# MOTOR_DRIVER.net
KiCad netlist of a schematic drawn in EAGLE
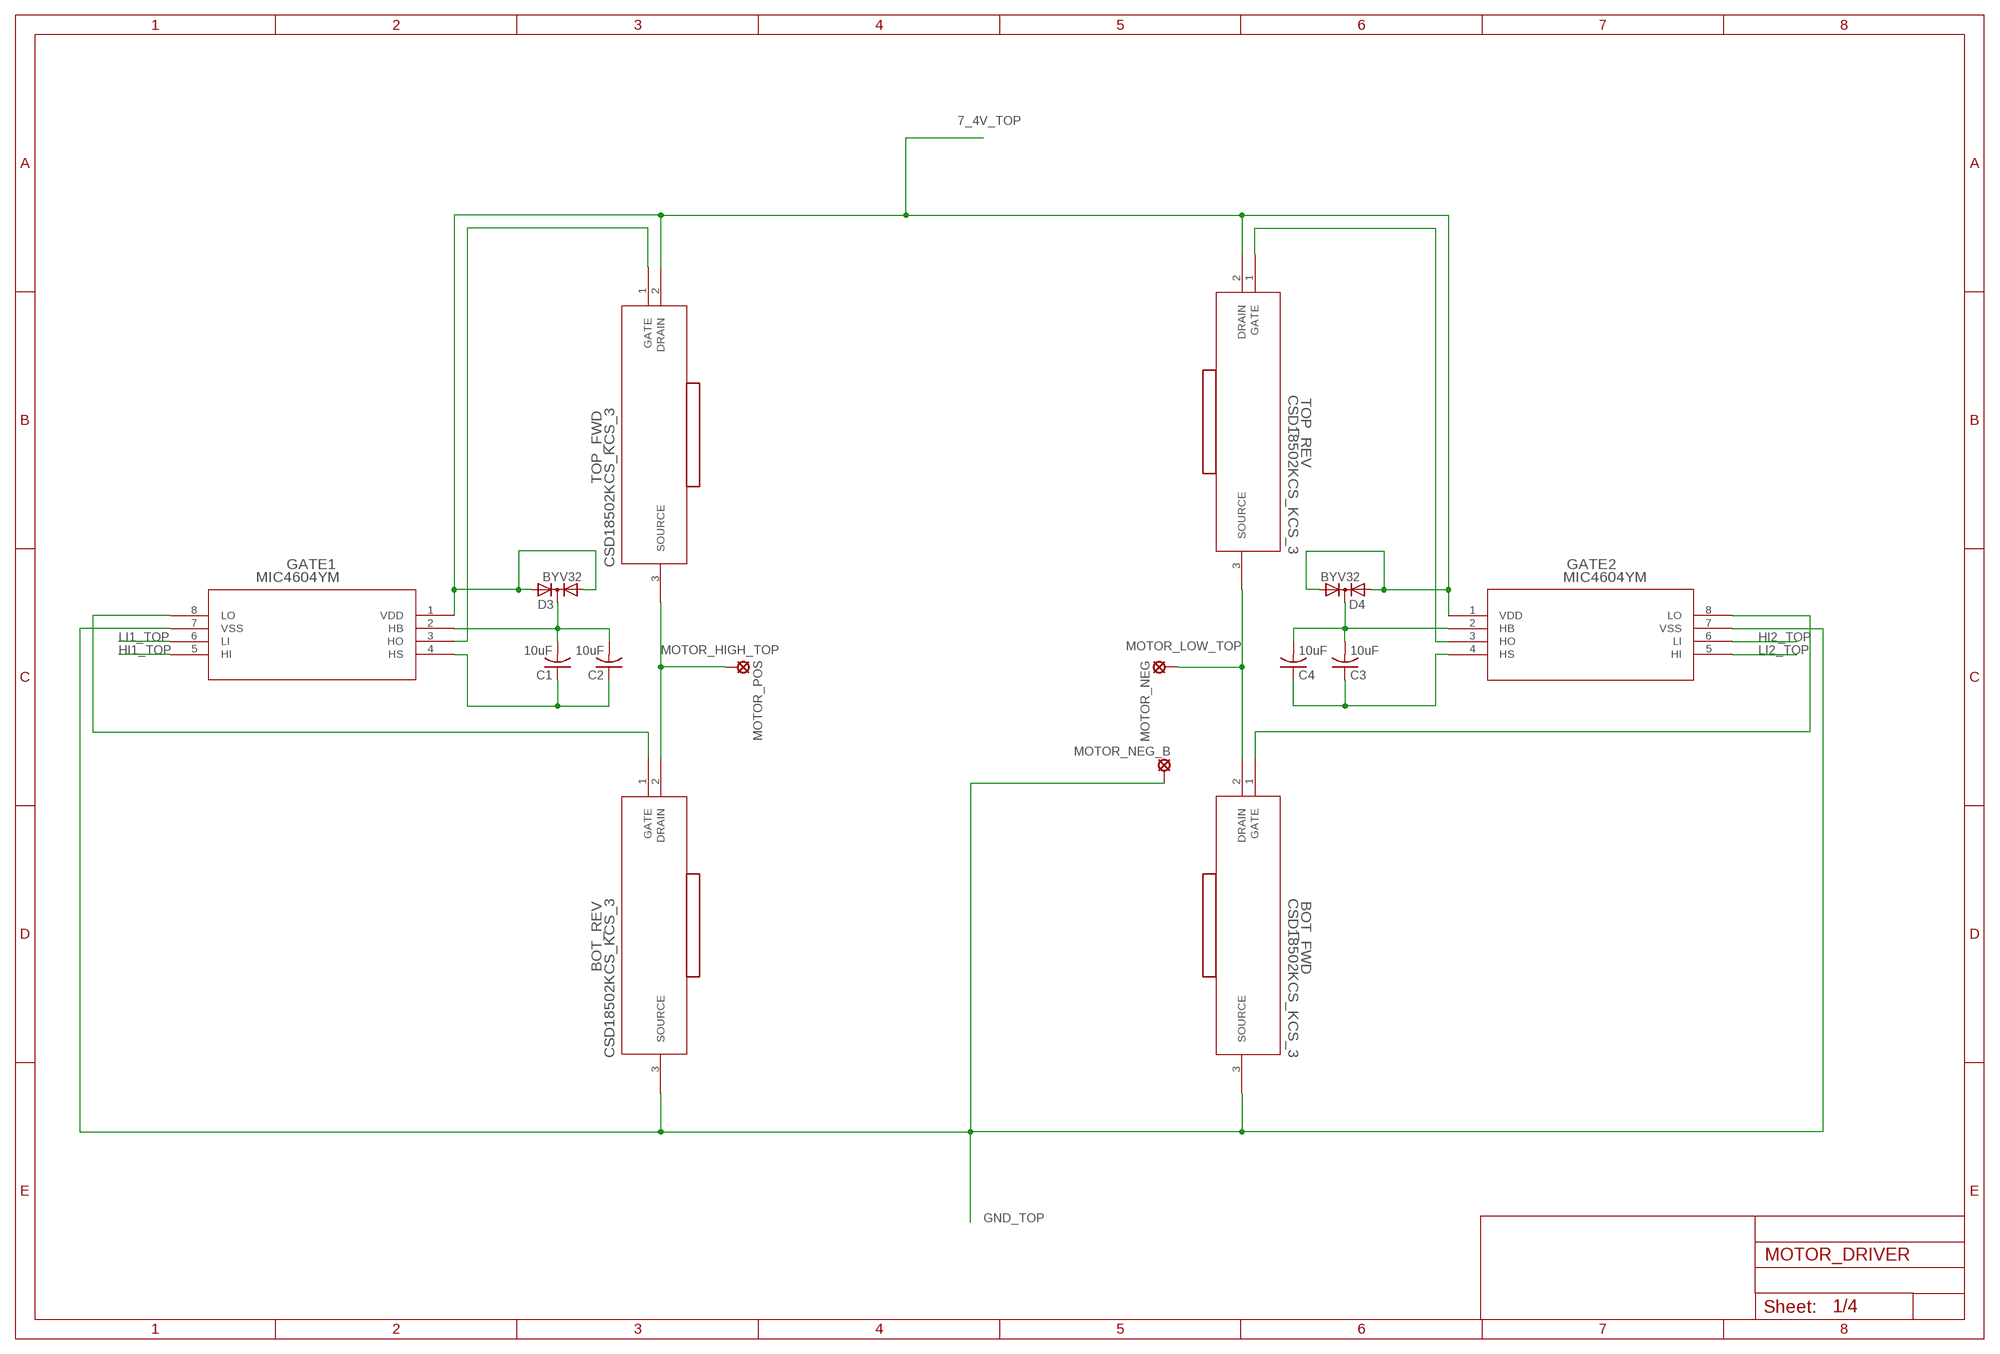
[diagram p0: schematic, sheet 1]
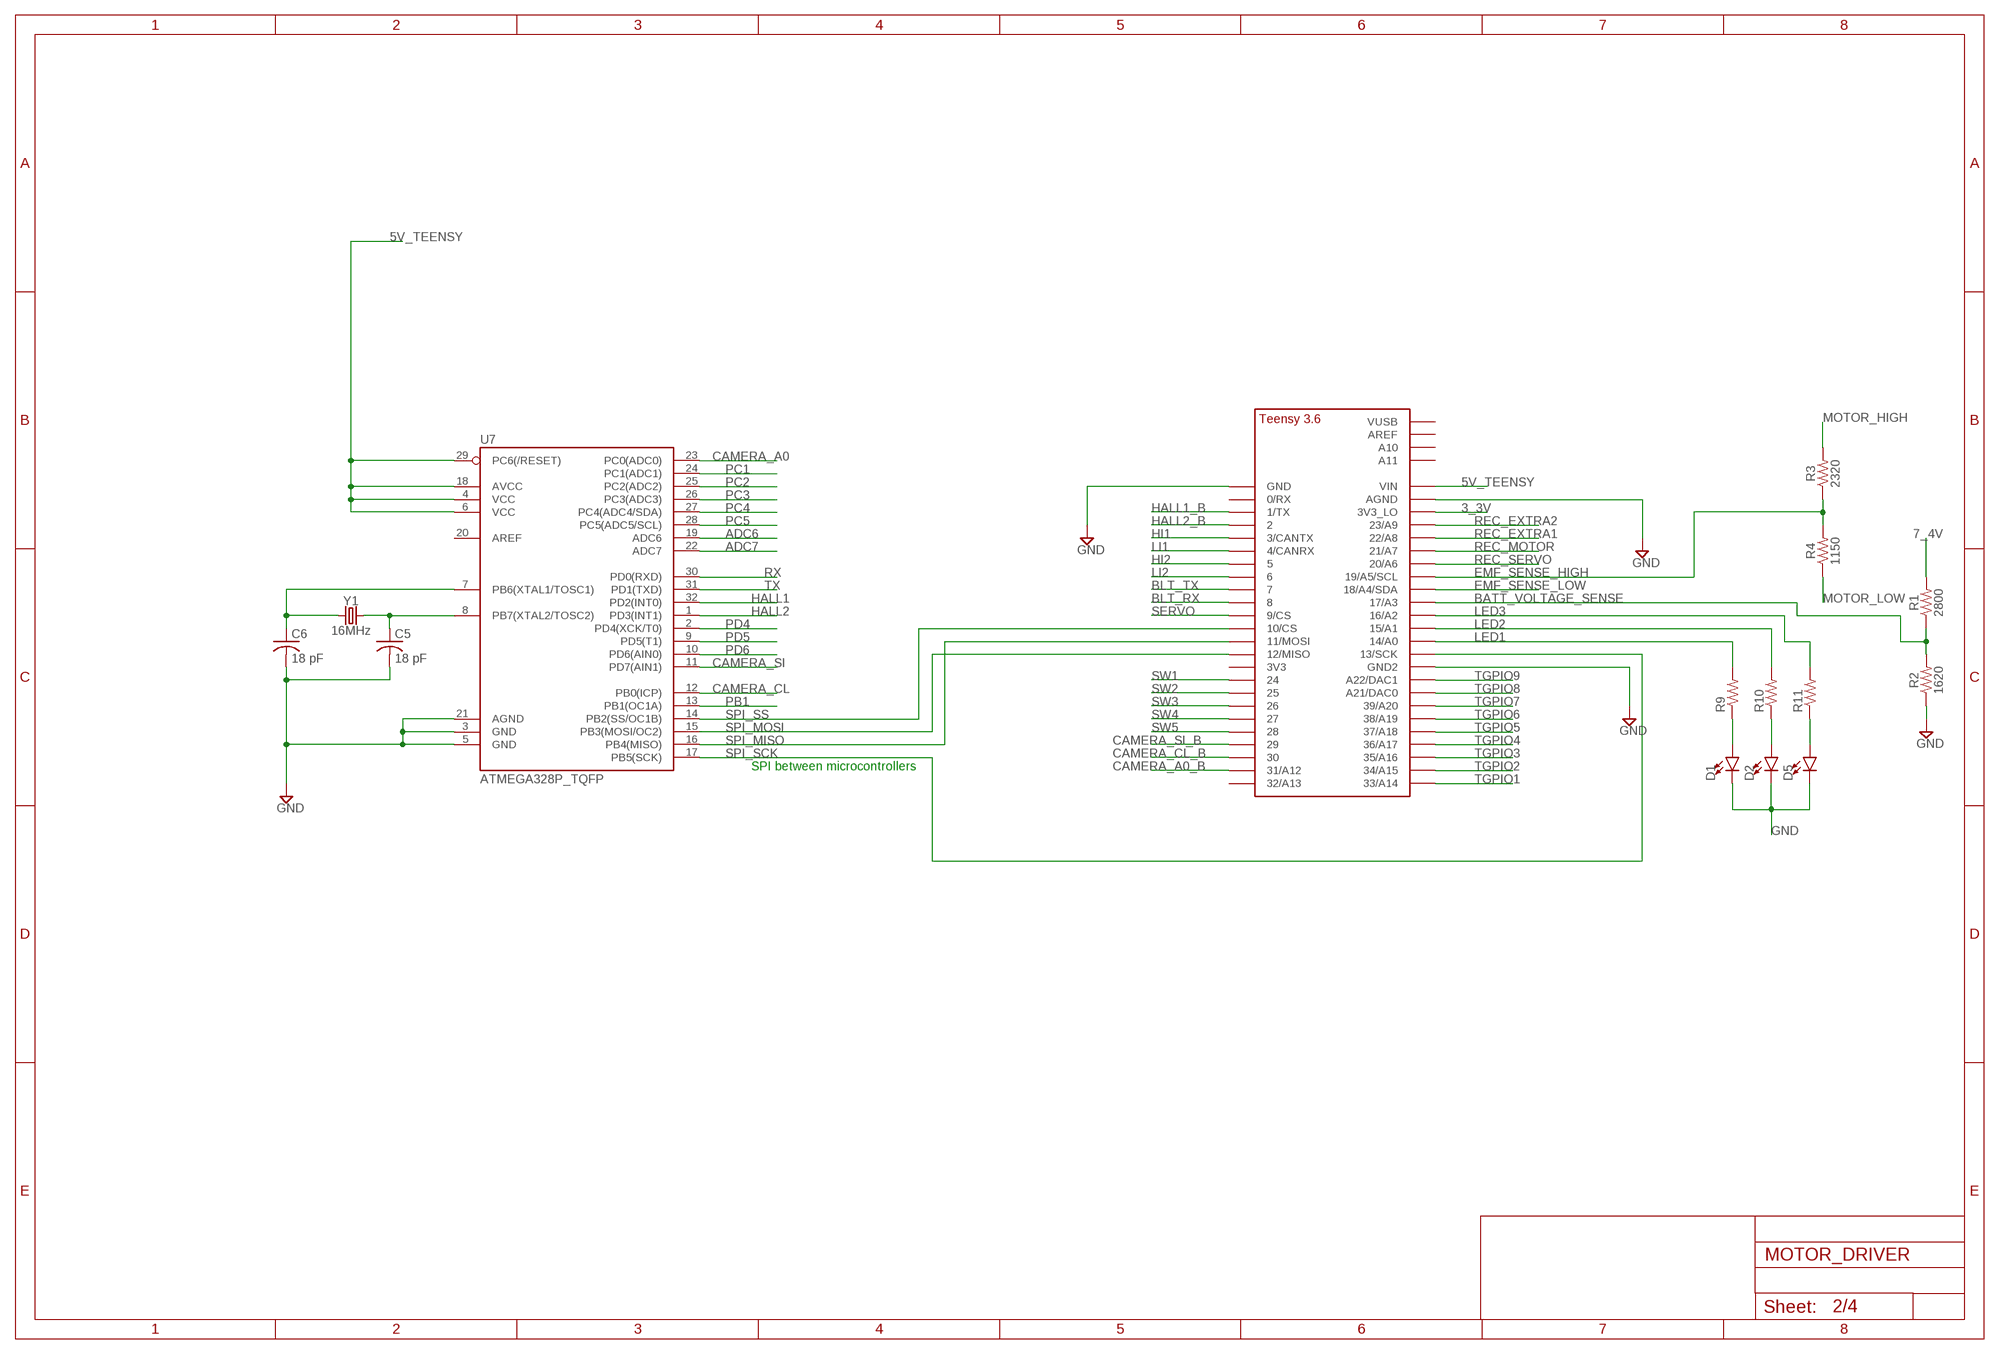
[diagram p1: schematic, sheet 2]
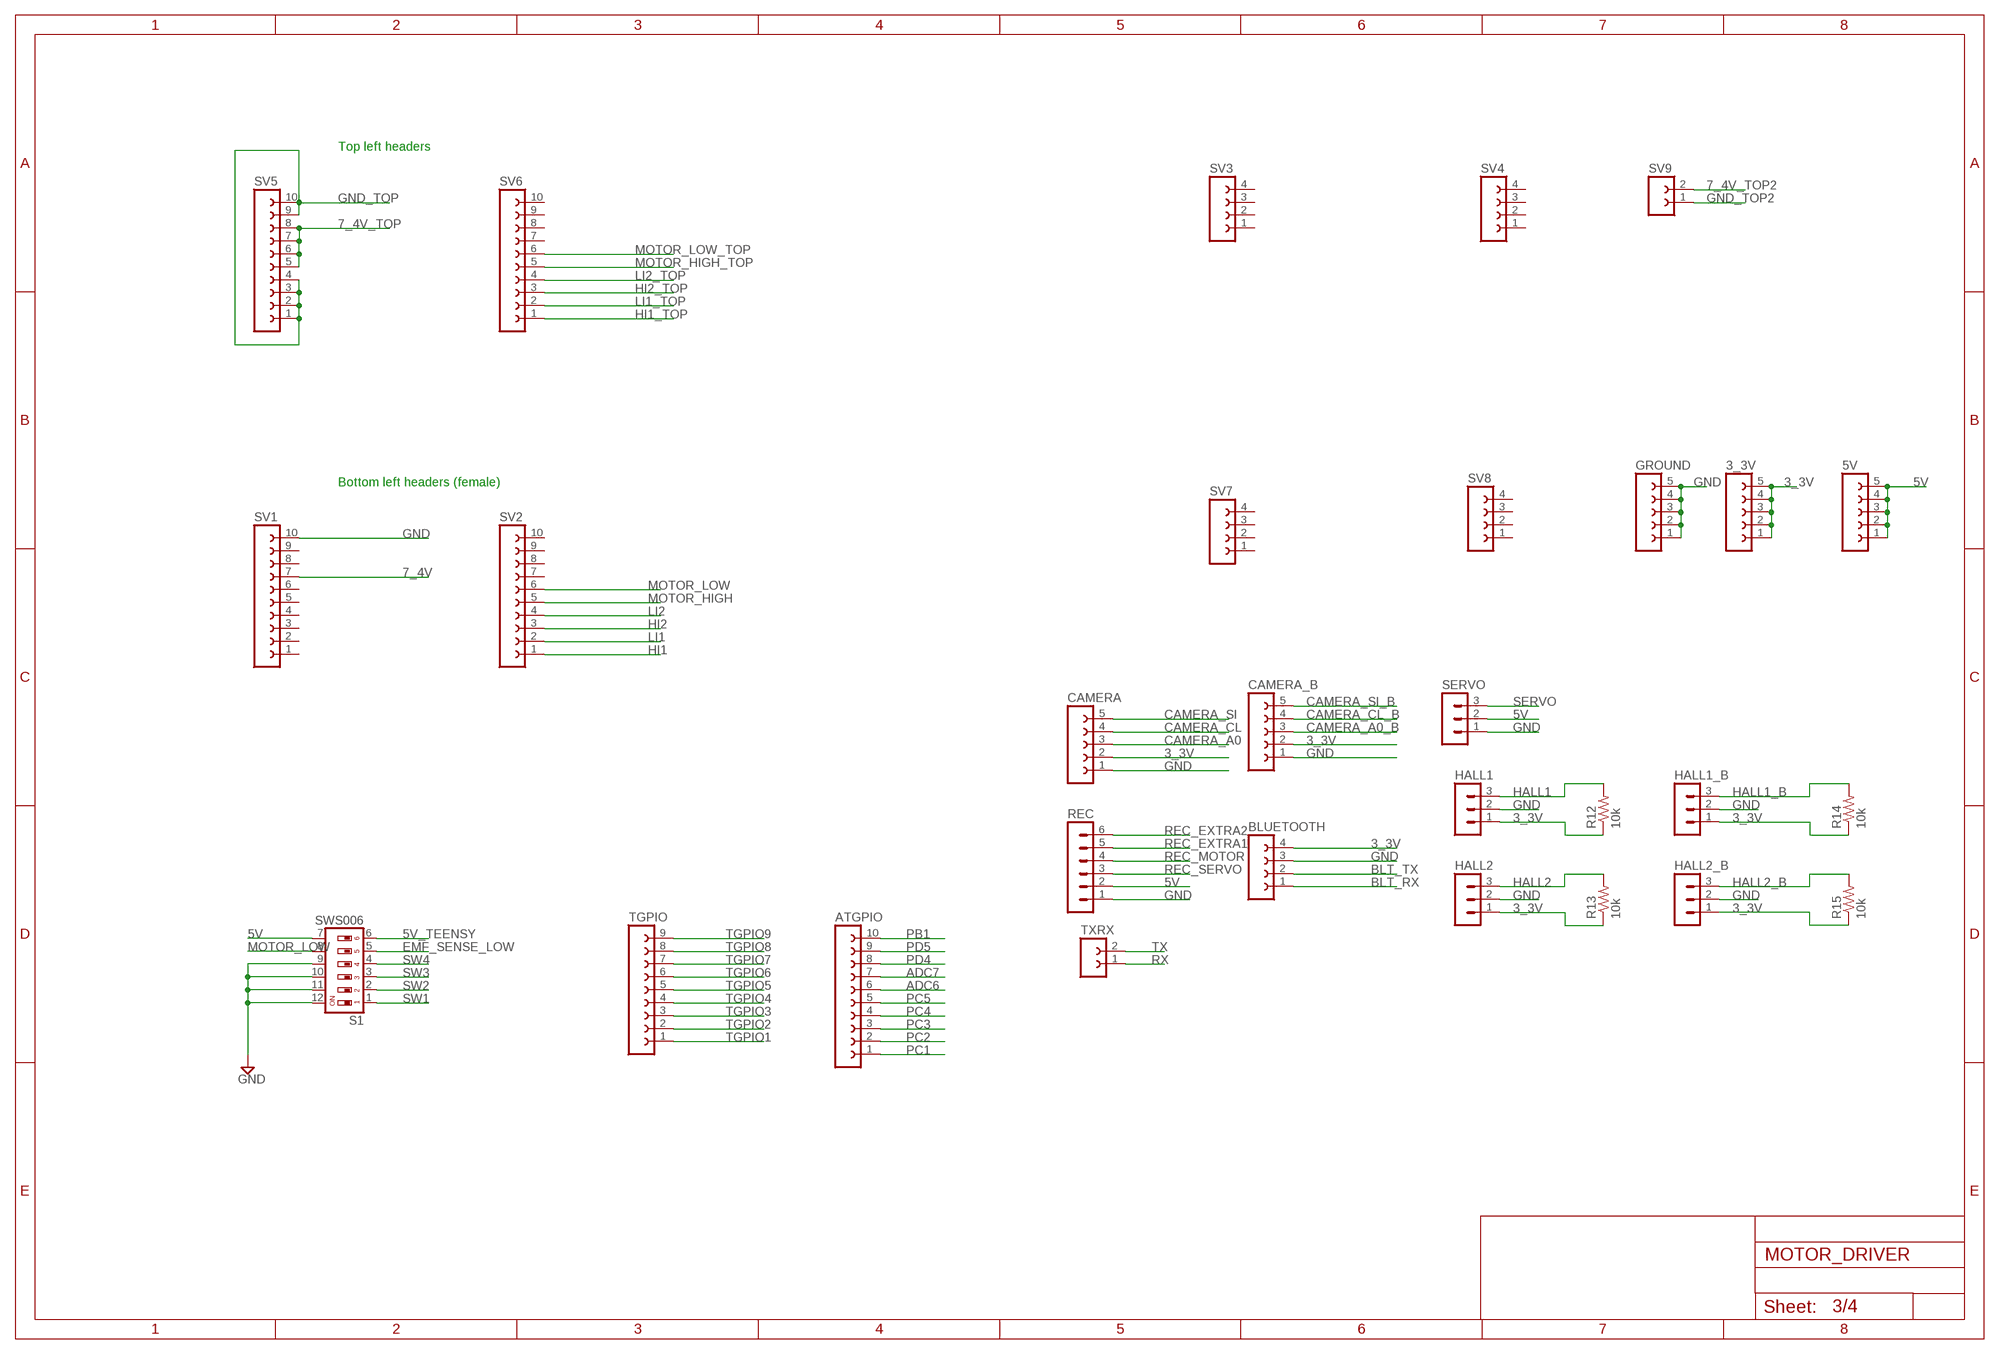
[diagram p2: schematic, sheet 3]
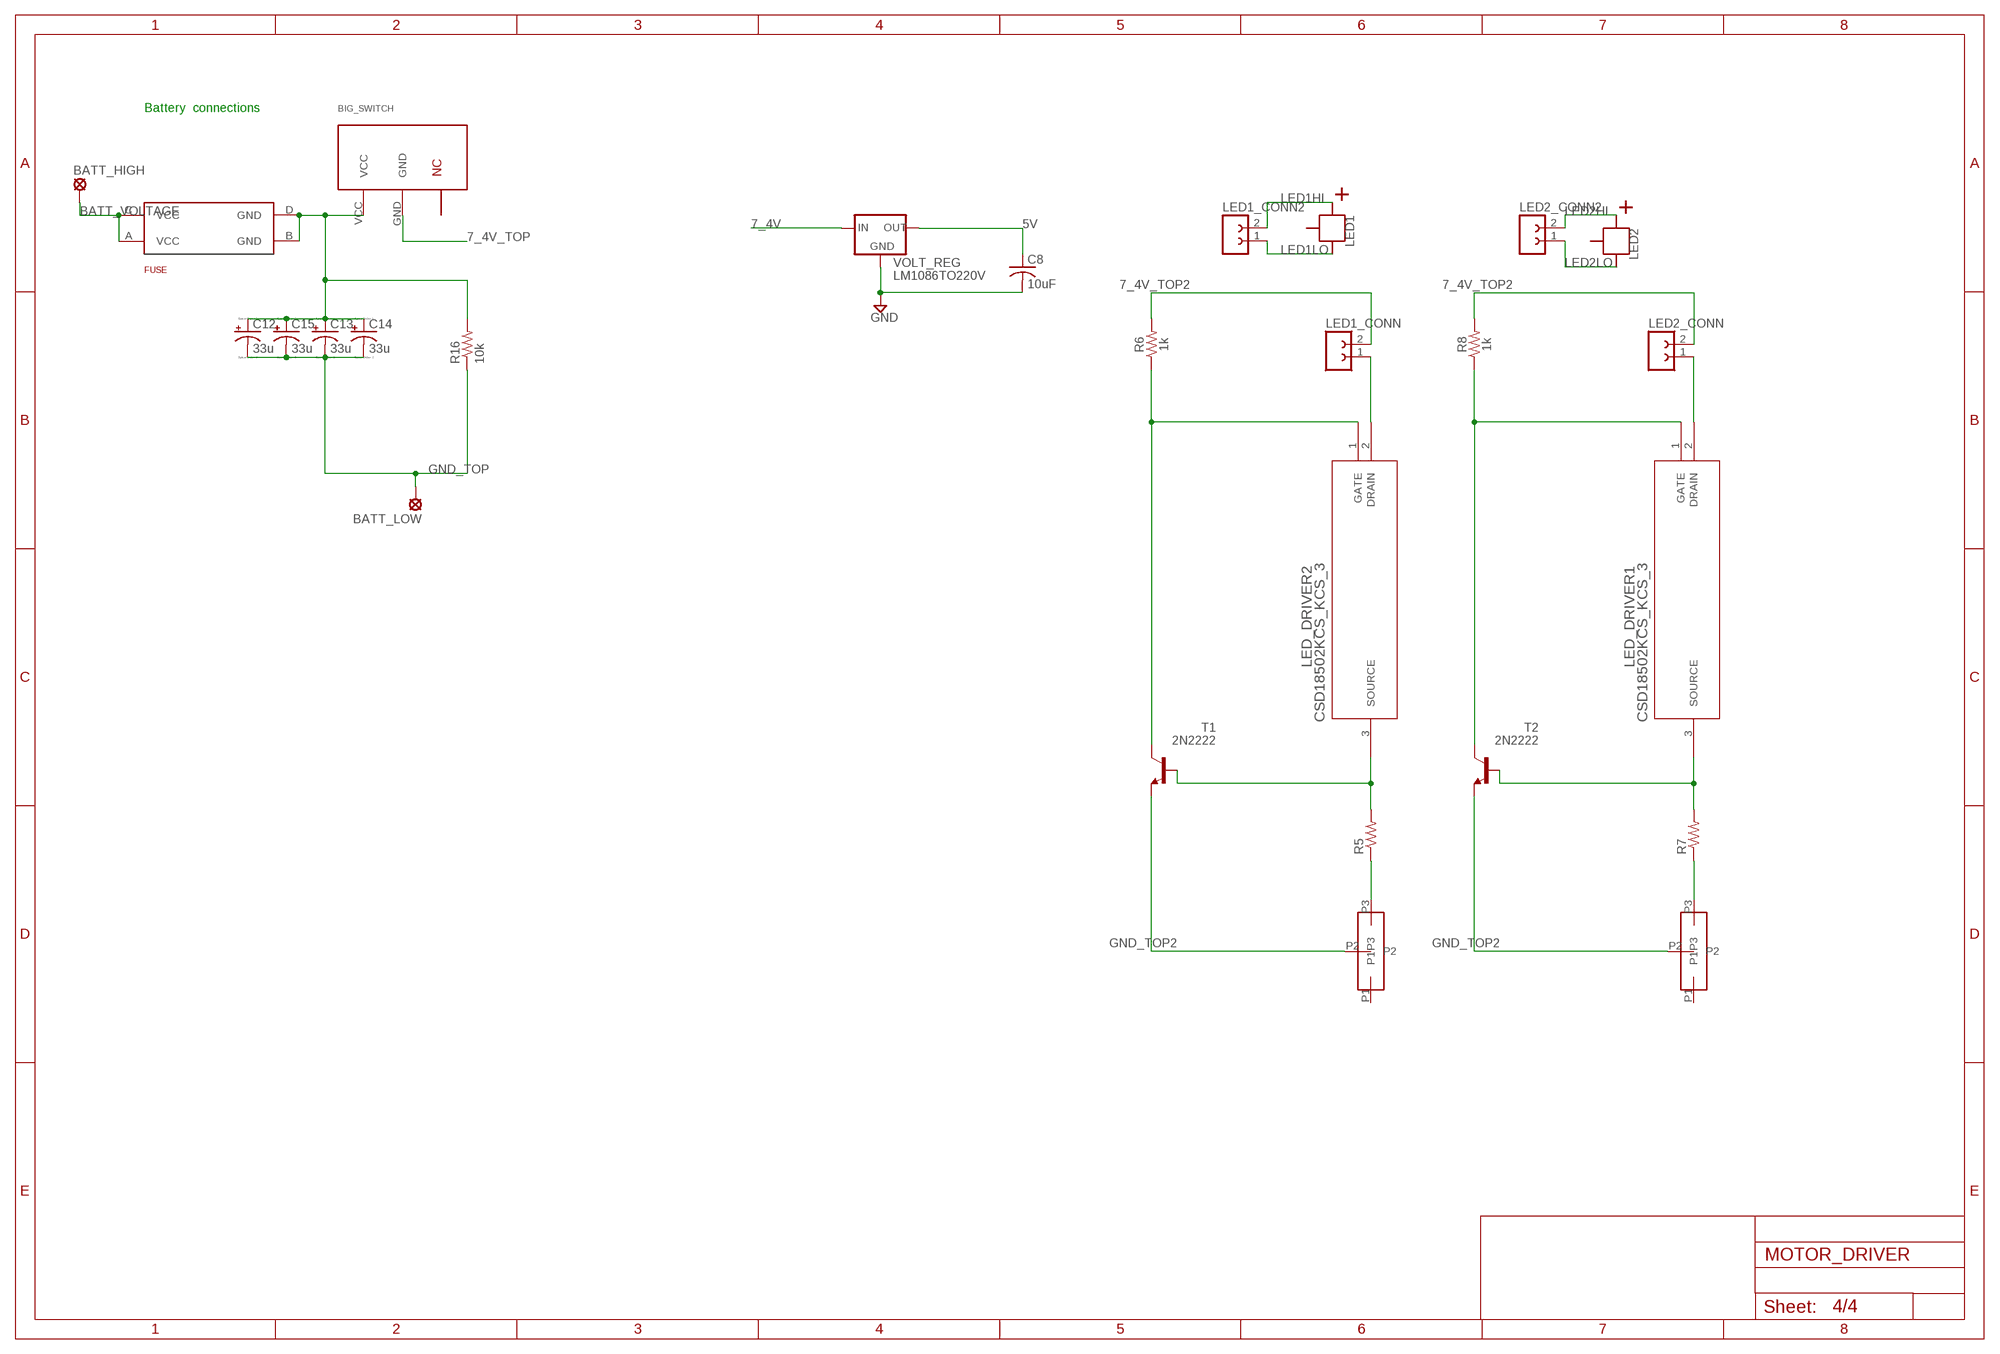
[diagram p3: schematic, sheet 4]

(export (version "E")
  (design (tool "Eeschema 10.0.6"))
  (components
    (comp (ref "C5")
      (value "18 pF")
      (footprint "eagle-import:C025-024X044")
      (libsource (lib "eagle-import") (part "C-US025-024X044"))
    )
    (comp (ref "C6")
      (value "18 pF")
      (footprint "eagle-import:C025-024X044")
      (libsource (lib "eagle-import") (part "C-US025-024X044"))
    )
    (comp (ref "D1")
      (value "LED0603")
      (footprint "eagle-import:LED-0603")
      (libsource (lib "eagle-import") (part "LED0603"))
    )
    (comp (ref "D2")
      (value "LED0603")
      (footprint "eagle-import:LED-0603")
      (libsource (lib "eagle-import") (part "LED0603"))
    )
    (comp (ref "D5")
      (value "LED0603")
      (footprint "eagle-import:LED-0603")
      (libsource (lib "eagle-import") (part "LED0603"))
    )
    (comp (ref "R1")
      (value "2800")
      (footprint "eagle-import:0805")
      (libsource (lib "eagle-import") (part "0.3OHM-0805-1/8W-1%"))
    )
    (comp (ref "R2")
      (value "1620")
      (footprint "eagle-import:0805")
      (libsource (lib "eagle-import") (part "0.3OHM-0805-1/8W-1%"))
    )
    (comp (ref "R3")
      (value "2320")
      (footprint "eagle-import:0805")
      (libsource (lib "eagle-import") (part "0.3OHM-0805-1/8W-1%"))
    )
    (comp (ref "R4")
      (value "1150")
      (footprint "eagle-import:0805")
      (libsource (lib "eagle-import") (part "0.3OHM-0805-1/8W-1%"))
    )
    (comp (ref "R9")
      (value "R-US_R0805")
      (footprint "eagle-import:R0805")
      (libsource (lib "eagle-import") (part "R-US_R0805"))
    )
    (comp (ref "R10")
      (value "R-US_R0805")
      (footprint "eagle-import:R0805")
      (libsource (lib "eagle-import") (part "R-US_R0805"))
    )
    (comp (ref "R11")
      (value "R-US_R0805")
      (footprint "eagle-import:R0805")
      (libsource (lib "eagle-import") (part "R-US_R0805"))
    )
    (comp (ref "U$1")
      (value "TEENSY_3.5/3.6_BASIC")
      (footprint "eagle-import:TEENSY_3.5_3.6_BASIC")
      (libsource (lib "eagle-import") (part "TEENSY_3.5/3.6_BASIC"))
    )
    (comp (ref "U7")
      (value "ATMEGA328P_TQFP")
      (footprint "eagle-import:TQFP32-08")
      (libsource (lib "eagle-import") (part "ATMEGA328P_TQFP"))
    )
    (comp (ref "Y1")
      (value "16MHz")
      (footprint "eagle-import:HC49US")
      (libsource (lib "eagle-import") (part "CRYSTAL-16MHZPTH-HC49US"))
    )
    (comp (ref "BATT_HIGH")
      (value "SE14")
      (footprint "eagle-import:SE14")
      (libsource (lib "eagle-import") (part "SE14"))
    )
    (comp (ref "BATT_LOW")
      (value "SE14")
      (footprint "eagle-import:SE14")
      (libsource (lib "eagle-import") (part "SE14"))
    )
    (comp (ref "BIG_SWITCH")
      (value "BIGSWITCH")
      (footprint "eagle-import:BIGSWITCH")
      (libsource (lib "eagle-import") (part "BIGSWITCH"))
    )
    (comp (ref "C8")
      (value "10uF")
      (footprint "eagle-import:C050-025X075")
      (libsource (lib "eagle-import") (part "C-US050-025X075"))
    )
    (comp (ref "C12")
      (value "33u")
      (footprint "eagle-import:153CLV-1010")
      (libsource (lib "eagle-import") (part "CPOL-US153CLV-1010"))
    )
    (comp (ref "C13")
      (value "33u")
      (footprint "eagle-import:153CLV-1010")
      (libsource (lib "eagle-import") (part "CPOL-US153CLV-1010"))
    )
    (comp (ref "C14")
      (value "33u")
      (footprint "eagle-import:153CLV-1010")
      (libsource (lib "eagle-import") (part "CPOL-US153CLV-1010"))
    )
    (comp (ref "C15")
      (value "33u")
      (footprint "eagle-import:153CLV-1010")
      (libsource (lib "eagle-import") (part "CPOL-US153CLV-1010"))
    )
    (comp (ref "FUSE")
      (value "FUSEHOLDER3588")
      (footprint "eagle-import:FUSEHOLDER3588")
      (libsource (lib "eagle-import") (part "FUSEHOLDER3588"))
    )
    (comp (ref "LED1")
      (value "CREE_XP")
      (footprint "eagle-import:XP")
      (libsource (lib "eagle-import") (part "CREE_XP"))
    )
    (comp (ref "LED1_CONN")
      (value "FE02-1")
      (footprint "eagle-import:FE02-1")
      (libsource (lib "eagle-import") (part "FE02-1"))
    )
    (comp (ref "LED1_CONN2")
      (value "FE02-1")
      (footprint "eagle-import:FE02-1")
      (libsource (lib "eagle-import") (part "FE02-1"))
    )
    (comp (ref "LED2")
      (value "CREE_XP")
      (footprint "eagle-import:XP")
      (libsource (lib "eagle-import") (part "CREE_XP"))
    )
    (comp (ref "LED2_CONN")
      (value "FE02-1")
      (footprint "eagle-import:FE02-1")
      (libsource (lib "eagle-import") (part "FE02-1"))
    )
    (comp (ref "LED2_CONN2")
      (value "FE02-1")
      (footprint "eagle-import:FE02-1")
      (libsource (lib "eagle-import") (part "FE02-1"))
    )
    (comp (ref "LED_DRIVER1")
      (value "CSD18502KCS_KCS_3")
      (footprint "eagle-import:KCS3")
      (fields (field (name "MANUFACTURER_PART_NUMBER") "csd18502kcs_kcs_3"))
      (libsource (lib "eagle-import") (part "CSD18502KCS_KCS_3"))
    )
    (comp (ref "LED_DRIVER2")
      (value "CSD18502KCS_KCS_3")
      (footprint "eagle-import:KCS3")
      (fields (field (name "MANUFACTURER_PART_NUMBER") "csd18502kcs_kcs_3"))
      (libsource (lib "eagle-import") (part "CSD18502KCS_KCS_3"))
    )
    (comp (ref "R5")
      (value "R-US_R2512")
      (footprint "eagle-import:R2512")
      (libsource (lib "eagle-import") (part "R-US_R2512"))
    )
    (comp (ref "R6")
      (value "1k")
      (footprint "eagle-import:AXIAL-0.3")
      (libsource (lib "eagle-import") (part "1KOHM-HORIZ-1/4W-1%"))
    )
    (comp (ref "R7")
      (value "R-US_R2512")
      (footprint "eagle-import:R2512")
      (libsource (lib "eagle-import") (part "R-US_R2512"))
    )
    (comp (ref "R8")
      (value "1k")
      (footprint "eagle-import:AXIAL-0.3")
      (libsource (lib "eagle-import") (part "1KOHM-HORIZ-1/4W-1%"))
    )
    (comp (ref "R16")
      (value "10k")
      (footprint "eagle-import:R0603")
      (libsource (lib "eagle-import") (part "resistor_R-US_R0603"))
    )
    (comp (ref "T1")
      (value "2N2222")
      (footprint "eagle-import:TO18")
      (libsource (lib "eagle-import") (part "2N2222"))
    )
    (comp (ref "T2")
      (value "2N2222")
      (footprint "eagle-import:TO18")
      (libsource (lib "eagle-import") (part "2N2222"))
    )
    (comp (ref "U$3")
      (value "POT")
      (footprint "eagle-import:POT")
      (libsource (lib "eagle-import") (part "POT"))
    )
    (comp (ref "U$7")
      (value "POT")
      (footprint "eagle-import:POT")
      (libsource (lib "eagle-import") (part "POT"))
    )
    (comp (ref "VOLT_REG")
      (value "LM1086TO220V")
      (footprint "eagle-import:TO220S")
      (libsource (lib "eagle-import") (part "LM1086TO220V"))
    )
    (comp (ref "3_3V")
      (value "FE05-1")
      (footprint "eagle-import:FE05-1")
      (libsource (lib "eagle-import") (part "FE05-1"))
    )
    (comp (ref "5V")
      (value "FE05-1")
      (footprint "eagle-import:FE05-1")
      (libsource (lib "eagle-import") (part "FE05-1"))
    )
    (comp (ref "ATGPIO")
      (value "FE10-1")
      (footprint "eagle-import:FE10")
      (libsource (lib "eagle-import") (part "FE10-1"))
    )
    (comp (ref "BLUETOOTH")
      (value "FE04-1")
      (footprint "eagle-import:FE04-1")
      (libsource (lib "eagle-import") (part "FE04-1"))
    )
    (comp (ref "CAMERA")
      (value "FE05-1")
      (footprint "eagle-import:FE05-1")
      (libsource (lib "eagle-import") (part "FE05-1"))
    )
    (comp (ref "CAMERA_B")
      (value "FE05-1")
      (footprint "eagle-import:FE05-1")
      (libsource (lib "eagle-import") (part "FE05-1"))
    )
    (comp (ref "GROUND")
      (value "FE05-1")
      (footprint "eagle-import:FE05-1")
      (libsource (lib "eagle-import") (part "FE05-1"))
    )
    (comp (ref "HALL1")
      (value "MA03-1")
      (footprint "eagle-import:MA03-1")
      (libsource (lib "eagle-import") (part "MA03-1"))
    )
    (comp (ref "HALL1_B")
      (value "MA03-1")
      (footprint "eagle-import:MA03-1")
      (libsource (lib "eagle-import") (part "MA03-1"))
    )
    (comp (ref "HALL2")
      (value "MA03-1")
      (footprint "eagle-import:MA03-1")
      (libsource (lib "eagle-import") (part "MA03-1"))
    )
    (comp (ref "HALL2_B")
      (value "MA03-1")
      (footprint "eagle-import:MA03-1")
      (libsource (lib "eagle-import") (part "MA03-1"))
    )
    (comp (ref "R12")
      (value "10k")
      (footprint "eagle-import:R0603")
      (libsource (lib "eagle-import") (part "resistor_R-US_R0603"))
    )
    (comp (ref "R13")
      (value "10k")
      (footprint "eagle-import:R0603")
      (libsource (lib "eagle-import") (part "resistor_R-US_R0603"))
    )
    (comp (ref "R14")
      (value "10k")
      (footprint "eagle-import:R0603")
      (libsource (lib "eagle-import") (part "resistor_R-US_R0603"))
    )
    (comp (ref "R15")
      (value "10k")
      (footprint "eagle-import:R0603")
      (libsource (lib "eagle-import") (part "resistor_R-US_R0603"))
    )
    (comp (ref "REC")
      (value "MA06-1")
      (footprint "eagle-import:MA06-1")
      (libsource (lib "eagle-import") (part "MA06-1"))
    )
    (comp (ref "S1")
      (value "SWS006")
      (footprint "eagle-import:SMS-006")
      (libsource (lib "eagle-import") (part "SWS006"))
    )
    (comp (ref "SERVO")
      (value "MA03-1")
      (footprint "eagle-import:MA03-1")
      (libsource (lib "eagle-import") (part "MA03-1"))
    )
    (comp (ref "SV1")
      (value "FE10-1")
      (footprint "eagle-import:FE10")
      (libsource (lib "eagle-import") (part "FE10-1"))
    )
    (comp (ref "SV2")
      (value "FE10-1")
      (footprint "eagle-import:FE10")
      (libsource (lib "eagle-import") (part "FE10-1"))
    )
    (comp (ref "SV3")
      (value "FE04-1")
      (footprint "eagle-import:FE04-1")
      (libsource (lib "eagle-import") (part "FE04-1"))
    )
    (comp (ref "SV4")
      (value "FE04-1")
      (footprint "eagle-import:FE04-1")
      (libsource (lib "eagle-import") (part "FE04-1"))
    )
    (comp (ref "SV5")
      (value "FE10-1")
      (footprint "eagle-import:FE10")
      (libsource (lib "eagle-import") (part "FE10-1"))
    )
    (comp (ref "SV6")
      (value "FE10-1")
      (footprint "eagle-import:FE10")
      (libsource (lib "eagle-import") (part "FE10-1"))
    )
    (comp (ref "SV7")
      (value "FE04-1")
      (footprint "eagle-import:FE04-1")
      (libsource (lib "eagle-import") (part "FE04-1"))
    )
    (comp (ref "SV8")
      (value "FE04-1")
      (footprint "eagle-import:FE04-1")
      (libsource (lib "eagle-import") (part "FE04-1"))
    )
    (comp (ref "SV9")
      (value "FE02-1")
      (footprint "eagle-import:FE02-1")
      (libsource (lib "eagle-import") (part "FE02-1"))
    )
    (comp (ref "TGPIO")
      (value "FE09-1")
      (footprint "eagle-import:FE09")
      (libsource (lib "eagle-import") (part "FE09-1"))
    )
    (comp (ref "TXRX")
      (value "FE02-1")
      (footprint "eagle-import:FE02-1")
      (libsource (lib "eagle-import") (part "FE02-1"))
    )
    (comp (ref "BOT_FWD")
      (value "CSD18502KCS_KCS_3")
      (footprint "eagle-import:KCS3")
      (fields (field (name "MANUFACTURER_PART_NUMBER") "csd18502kcs_kcs_3"))
      (libsource (lib "eagle-import") (part "CSD18502KCS_KCS_3"))
    )
    (comp (ref "BOT_REV")
      (value "CSD18502KCS_KCS_3")
      (footprint "eagle-import:KCS3")
      (fields (field (name "MANUFACTURER_PART_NUMBER") "csd18502kcs_kcs_3"))
      (libsource (lib "eagle-import") (part "CSD18502KCS_KCS_3"))
    )
    (comp (ref "C1")
      (value "10uF")
      (footprint "eagle-import:C025-050X050")
      (libsource (lib "eagle-import") (part "C-US025-050X050"))
    )
    (comp (ref "C2")
      (value "10uF")
      (footprint "eagle-import:C025-050X050")
      (libsource (lib "eagle-import") (part "C-US025-050X050"))
    )
    (comp (ref "C3")
      (value "10uF")
      (footprint "eagle-import:C025-050X050")
      (libsource (lib "eagle-import") (part "C-US025-050X050"))
    )
    (comp (ref "C4")
      (value "10uF")
      (footprint "eagle-import:C025-050X050")
      (libsource (lib "eagle-import") (part "C-US025-050X050"))
    )
    (comp (ref "D3")
      (value "BYV32")
      (footprint "eagle-import:TO220ABS")
      (libsource (lib "eagle-import") (part "BYV32"))
    )
    (comp (ref "D4")
      (value "BYV32")
      (footprint "eagle-import:TO220ABS")
      (libsource (lib "eagle-import") (part "BYV32"))
    )
    (comp (ref "GATE1")
      (value "MIC4604YM")
      (footprint "eagle-import:SOIC-8_M")
      (fields (field (name "MANUFACTURER_PART_NUMBER") "mic4604ym"))
      (libsource (lib "eagle-import") (part "MIC4604YM"))
    )
    (comp (ref "GATE2")
      (value "MIC4604YM")
      (footprint "eagle-import:SOIC-8_M")
      (fields (field (name "MANUFACTURER_PART_NUMBER") "mic4604ym"))
      (libsource (lib "eagle-import") (part "MIC4604YM"))
    )
    (comp (ref "MOTOR_NEG")
      (value "SE14")
      (footprint "eagle-import:SE14")
      (libsource (lib "eagle-import") (part "SE14"))
    )
    (comp (ref "MOTOR_NEG_B")
      (value "SE14")
      (footprint "eagle-import:SE14")
      (libsource (lib "eagle-import") (part "SE14"))
    )
    (comp (ref "MOTOR_POS")
      (value "SE14")
      (footprint "eagle-import:SE14")
      (libsource (lib "eagle-import") (part "SE14"))
    )
    (comp (ref "TOP_FWD")
      (value "CSD18502KCS_KCS_3")
      (footprint "eagle-import:KCS3")
      (fields (field (name "MANUFACTURER_PART_NUMBER") "csd18502kcs_kcs_3"))
      (libsource (lib "eagle-import") (part "CSD18502KCS_KCS_3"))
    )
    (comp (ref "TOP_REV")
      (value "CSD18502KCS_KCS_3")
      (footprint "eagle-import:KCS3")
      (fields (field (name "MANUFACTURER_PART_NUMBER") "csd18502kcs_kcs_3"))
      (libsource (lib "eagle-import") (part "CSD18502KCS_KCS_3"))
    )
    (comp (ref "U$2")
      (value "HEATSINK")
      (footprint "eagle-import:HEATSINK")
      (libsource (lib "eagle-import") (part "HEATSINK"))
    )
    (comp (ref "U$4")
      (value "HEATSINK")
      (footprint "eagle-import:HEATSINK")
      (libsource (lib "eagle-import") (part "HEATSINK"))
    )
    (comp (ref "U$5")
      (value "HEATSINK")
      (footprint "eagle-import:HEATSINK")
      (libsource (lib "eagle-import") (part "HEATSINK"))
    )
    (comp (ref "U$6")
      (value "HEATSINK")
      (footprint "eagle-import:HEATSINK")
      (libsource (lib "eagle-import") (part "HEATSINK"))
    )
  )
  (nets
    (net (code "1") (name "3_3V") (class "Default")
      (node (ref "3_3V") (pin "1") (pinfunction "1_1") (pintype "passive"))
      (node (ref "3_3V") (pin "2") (pinfunction "2_2") (pintype "passive"))
      (node (ref "3_3V") (pin "3") (pinfunction "3_3") (pintype "passive"))
      (node (ref "3_3V") (pin "4") (pinfunction "4_4") (pintype "passive"))
      (node (ref "3_3V") (pin "5") (pinfunction "5_5") (pintype "passive"))
      (node (ref "BLUETOOTH") (pin "4") (pinfunction "4_4") (pintype "passive"))
      (node (ref "CAMERA") (pin "2") (pinfunction "2_2") (pintype "passive"))
      (node (ref "CAMERA_B") (pin "2") (pinfunction "2_2") (pintype "passive"))
      (node (ref "HALL1") (pin "1") (pinfunction "1_1") (pintype "passive"))
      (node (ref "HALL1_B") (pin "1") (pinfunction "1_1") (pintype "passive"))
      (node (ref "HALL2") (pin "1") (pinfunction "1_1") (pintype "passive"))
      (node (ref "HALL2_B") (pin "1") (pinfunction "1_1") (pintype "passive"))
      (node (ref "R12") (pin "1") (pinfunction "1_1") (pintype "passive"))
      (node (ref "R13") (pin "1") (pinfunction "1_1") (pintype "passive"))
      (node (ref "R14") (pin "1") (pinfunction "1_1") (pintype "passive"))
      (node (ref "R15") (pin "1") (pinfunction "1_1") (pintype "passive"))
      (node (ref "U$1") (pin "3V3_LO") (pinfunction "3V3_LO_3V3_LO") (pintype "bidirectional"))
    )
    (net (code "2") (name "5V") (class "Default")
      (node (ref "5V") (pin "1") (pinfunction "1_1") (pintype "passive"))
      (node (ref "5V") (pin "2") (pinfunction "2_2") (pintype "passive"))
      (node (ref "5V") (pin "3") (pinfunction "3_3") (pintype "passive"))
      (node (ref "5V") (pin "4") (pinfunction "4_4") (pintype "passive"))
      (node (ref "5V") (pin "5") (pinfunction "5_5") (pintype "passive"))
      (node (ref "C8") (pin "1") (pinfunction "1_1") (pintype "passive"))
      (node (ref "REC") (pin "2") (pinfunction "2_2") (pintype "passive"))
      (node (ref "S1") (pin "7") (pinfunction "7_7") (pintype "passive"))
      (node (ref "SERVO") (pin "2") (pinfunction "2_2") (pintype "passive"))
      (node (ref "VOLT_REG") (pin "2") (pinfunction "OUT_2") (pintype "passive"))
    )
    (net (code "3") (name "5V_TEENSY") (class "Default")
      (node (ref "S1") (pin "6") (pinfunction "6_6") (pintype "passive"))
      (node (ref "U$1") (pin "VIN") (pinfunction "VIN_VIN") (pintype "bidirectional"))
      (node (ref "U7") (pin "18") (pinfunction "AVCC_18") (pintype "bidirectional"))
      (node (ref "U7") (pin "29") (pinfunction "PC6(/RESET)_29") (pintype "bidirectional"))
      (node (ref "U7") (pin "4") (pinfunction "VCC_4") (pintype "bidirectional"))
      (node (ref "U7") (pin "6") (pinfunction "VCC_6") (pintype "bidirectional"))
    )
    (net (code "4") (name "7_4V") (class "Default")
      (node (ref "R1") (pin "2") (pinfunction "2_2") (pintype "passive"))
      (node (ref "SV1") (pin "7") (pinfunction "7_7") (pintype "passive"))
      (node (ref "VOLT_REG") (pin "3") (pinfunction "IN_3") (pintype "input"))
    )
    (net (code "5") (name "7_4V_TOP") (class "Default")
      (node (ref "BIG_SWITCH") (pin "GND") (pinfunction "GND_GND") (pintype "power_in"))
      (node (ref "D3") (pin "A1") (pinfunction "A1_A1") (pintype "passive"))
      (node (ref "D3") (pin "A2") (pinfunction "A2_A2") (pintype "passive"))
      (node (ref "D4") (pin "A1") (pinfunction "A1_A1") (pintype "passive"))
      (node (ref "D4") (pin "A2") (pinfunction "A2_A2") (pintype "passive"))
      (node (ref "GATE1") (pin "1") (pinfunction "VDD_1") (pintype "power_in"))
      (node (ref "GATE2") (pin "1") (pinfunction "VDD_1") (pintype "power_in"))
      (node (ref "SV5") (pin "5") (pinfunction "5_5") (pintype "passive"))
      (node (ref "SV5") (pin "6") (pinfunction "6_6") (pintype "passive"))
      (node (ref "SV5") (pin "7") (pinfunction "7_7") (pintype "passive"))
      (node (ref "SV5") (pin "8") (pinfunction "8_8") (pintype "passive"))
      (node (ref "TOP_FWD") (pin "2") (pinfunction "DRAIN_2") (pintype "passive"))
      (node (ref "TOP_REV") (pin "2") (pinfunction "DRAIN_2") (pintype "passive"))
    )
    (net (code "6") (name "7_4V_TOP2") (class "Default")
      (node (ref "LED1_CONN") (pin "2") (pinfunction "2_2") (pintype "passive"))
      (node (ref "LED2_CONN") (pin "2") (pinfunction "2_2") (pintype "passive"))
      (node (ref "R6") (pin "P$2") (pinfunction "2_P$2") (pintype "passive"))
      (node (ref "R8") (pin "P$2") (pinfunction "2_P$2") (pintype "passive"))
      (node (ref "SV9") (pin "2") (pinfunction "2_2") (pintype "passive"))
    )
    (net (code "7") (name "ADC6") (class "Default")
      (node (ref "ATGPIO") (pin "6") (pinfunction "6_6") (pintype "passive"))
      (node (ref "U7") (pin "19") (pinfunction "ADC6_19") (pintype "bidirectional"))
    )
    (net (code "8") (name "ADC7") (class "Default")
      (node (ref "ATGPIO") (pin "7") (pinfunction "7_7") (pintype "passive"))
      (node (ref "U7") (pin "22") (pinfunction "ADC7_22") (pintype "bidirectional"))
    )
    (net (code "9") (name "BATT_VOLTAGE") (class "Default")
      (node (ref "BATT_HIGH") (pin "MP") (pinfunction "MP_MP") (pintype "passive"))
      (node (ref "FUSE") (pin "A") (pinfunction "VCC_A") (pintype "power_in"))
      (node (ref "FUSE") (pin "C") (pinfunction "VCC_C") (pintype "power_in"))
    )
    (net (code "10") (name "BATT_VOLTAGE_SENSE") (class "Default")
      (node (ref "R1") (pin "1") (pinfunction "1_1") (pintype "passive"))
      (node (ref "R2") (pin "2") (pinfunction "2_2") (pintype "passive"))
      (node (ref "U$1") (pin "17/A3") (pinfunction "17/A3_17/A3") (pintype "bidirectional"))
    )
    (net (code "11") (name "BLT_RX") (class "Default")
      (node (ref "BLUETOOTH") (pin "1") (pinfunction "1_1") (pintype "passive"))
      (node (ref "U$1") (pin "8") (pinfunction "8_8") (pintype "bidirectional"))
    )
    (net (code "12") (name "BLT_TX") (class "Default")
      (node (ref "BLUETOOTH") (pin "2") (pinfunction "2_2") (pintype "passive"))
      (node (ref "U$1") (pin "7") (pinfunction "7_7") (pintype "bidirectional"))
    )
    (net (code "13") (name "CAMERA_A0") (class "Default")
      (node (ref "CAMERA") (pin "3") (pinfunction "3_3") (pintype "passive"))
      (node (ref "U7") (pin "23") (pinfunction "PC0(ADC0)_23") (pintype "bidirectional"))
    )
    (net (code "14") (name "CAMERA_A0_B") (class "Default")
      (node (ref "CAMERA_B") (pin "3") (pinfunction "3_3") (pintype "passive"))
      (node (ref "U$1") (pin "31/A12") (pinfunction "31/A12_31/A12") (pintype "bidirectional"))
    )
    (net (code "15") (name "CAMERA_CL") (class "Default")
      (node (ref "CAMERA") (pin "4") (pinfunction "4_4") (pintype "passive"))
      (node (ref "U7") (pin "12") (pinfunction "PB0(ICP)_12") (pintype "bidirectional"))
    )
    (net (code "16") (name "CAMERA_CL_B") (class "Default")
      (node (ref "CAMERA_B") (pin "4") (pinfunction "4_4") (pintype "passive"))
      (node (ref "U$1") (pin "30") (pinfunction "30_30") (pintype "bidirectional"))
    )
    (net (code "17") (name "CAMERA_SI") (class "Default")
      (node (ref "CAMERA") (pin "5") (pinfunction "5_5") (pintype "passive"))
      (node (ref "U7") (pin "11") (pinfunction "PD7(AIN1)_11") (pintype "bidirectional"))
    )
    (net (code "18") (name "CAMERA_SI_B") (class "Default")
      (node (ref "CAMERA_B") (pin "5") (pinfunction "5_5") (pintype "passive"))
      (node (ref "U$1") (pin "29") (pinfunction "29_29") (pintype "bidirectional"))
    )
    (net (code "19") (name "EMF_SENSE_HIGH") (class "Default")
      (node (ref "R3") (pin "1") (pinfunction "1_1") (pintype "passive"))
      (node (ref "R4") (pin "2") (pinfunction "2_2") (pintype "passive"))
      (node (ref "U$1") (pin "19/A5/SCL") (pinfunction "19/A5/SCL_19/A5/SCL") (pintype "bidirectional"))
    )
    (net (code "20") (name "EMF_SENSE_LOW") (class "Default")
      (node (ref "S1") (pin "5") (pinfunction "5_5") (pintype "passive"))
      (node (ref "U$1") (pin "18/A4/SDA") (pinfunction "18/A4/SDA_18/A4/SDA") (pintype "bidirectional"))
    )
    (net (code "21") (name "GND") (class "Default")
      (node (ref "BLUETOOTH") (pin "3") (pinfunction "3_3") (pintype "passive"))
      (node (ref "C5") (pin "2") (pinfunction "2_2") (pintype "passive"))
      (node (ref "C6") (pin "2") (pinfunction "2_2") (pintype "passive"))
      (node (ref "C8") (pin "2") (pinfunction "2_2") (pintype "passive"))
      (node (ref "CAMERA") (pin "1") (pinfunction "1_1") (pintype "passive"))
      (node (ref "CAMERA_B") (pin "1") (pinfunction "1_1") (pintype "passive"))
      (node (ref "D1") (pin "C") (pinfunction "C_C") (pintype "passive"))
      (node (ref "D2") (pin "C") (pinfunction "C_C") (pintype "passive"))
      (node (ref "D5") (pin "C") (pinfunction "C_C") (pintype "passive"))
      (node (ref "GROUND") (pin "1") (pinfunction "1_1") (pintype "passive"))
      (node (ref "GROUND") (pin "2") (pinfunction "2_2") (pintype "passive"))
      (node (ref "GROUND") (pin "3") (pinfunction "3_3") (pintype "passive"))
      (node (ref "GROUND") (pin "4") (pinfunction "4_4") (pintype "passive"))
      (node (ref "GROUND") (pin "5") (pinfunction "5_5") (pintype "passive"))
      (node (ref "HALL1") (pin "2") (pinfunction "2_2") (pintype "passive"))
      (node (ref "HALL1_B") (pin "2") (pinfunction "2_2") (pintype "passive"))
      (node (ref "HALL2") (pin "2") (pinfunction "2_2") (pintype "passive"))
      (node (ref "HALL2_B") (pin "2") (pinfunction "2_2") (pintype "passive"))
      (node (ref "R2") (pin "1") (pinfunction "1_1") (pintype "passive"))
      (node (ref "REC") (pin "1") (pinfunction "1_1") (pintype "passive"))
      (node (ref "S1") (pin "10") (pinfunction "10_10") (pintype "passive"))
      (node (ref "S1") (pin "11") (pinfunction "11_11") (pintype "passive"))
      (node (ref "S1") (pin "12") (pinfunction "12_12") (pintype "passive"))
      (node (ref "S1") (pin "9") (pinfunction "9_9") (pintype "passive"))
      (node (ref "SERVO") (pin "1") (pinfunction "1_1") (pintype "passive"))
      (node (ref "SV1") (pin "10") (pinfunction "10_10") (pintype "passive"))
      (node (ref "U$1") (pin "AGND") (pinfunction "AGND_AGND") (pintype "bidirectional"))
      (node (ref "U$1") (pin "GND") (pinfunction "GND_GND") (pintype "bidirectional"))
      (node (ref "U$1") (pin "GND2") (pinfunction "GND2_GND2") (pintype "bidirectional"))
      (node (ref "U7") (pin "21") (pinfunction "AGND_21") (pintype "bidirectional"))
      (node (ref "U7") (pin "3") (pinfunction "GND_3") (pintype "bidirectional"))
      (node (ref "U7") (pin "5") (pinfunction "GND_5") (pintype "bidirectional"))
      (node (ref "VOLT_REG") (pin "1") (pinfunction "GND_1") (pintype "input"))
    )
    (net (code "22") (name "GND_TOP") (class "Default")
      (node (ref "BATT_LOW") (pin "MP") (pinfunction "MP_MP") (pintype "passive"))
      (node (ref "BOT_FWD") (pin "3") (pinfunction "SOURCE_3") (pintype "passive"))
      (node (ref "BOT_REV") (pin "3") (pinfunction "SOURCE_3") (pintype "passive"))
      (node (ref "C12") (pin "-") (pinfunction "-_-") (pintype "passive"))
      (node (ref "C13") (pin "-") (pinfunction "-_-") (pintype "passive"))
      (node (ref "C14") (pin "-") (pinfunction "-_-") (pintype "passive"))
      (node (ref "C15") (pin "-") (pinfunction "-_-") (pintype "passive"))
      (node (ref "GATE1") (pin "7") (pinfunction "VSS_7") (pintype "power_in"))
      (node (ref "GATE2") (pin "7") (pinfunction "VSS_7") (pintype "power_in"))
      (node (ref "MOTOR_NEG_B") (pin "MP") (pinfunction "MP_MP") (pintype "passive"))
      (node (ref "R16") (pin "1") (pinfunction "1_1") (pintype "passive"))
      (node (ref "SV5") (pin "1") (pinfunction "1_1") (pintype "passive"))
      (node (ref "SV5") (pin "10") (pinfunction "10_10") (pintype "passive"))
      (node (ref "SV5") (pin "2") (pinfunction "2_2") (pintype "passive"))
      (node (ref "SV5") (pin "3") (pinfunction "3_3") (pintype "passive"))
      (node (ref "SV5") (pin "4") (pinfunction "4_4") (pintype "passive"))
      (node (ref "SV5") (pin "9") (pinfunction "9_9") (pintype "passive"))
    )
    (net (code "23") (name "GND_TOP2") (class "Default")
      (node (ref "SV9") (pin "1") (pinfunction "1_1") (pintype "passive"))
      (node (ref "T1") (pin "1") (pinfunction "E_1") (pintype "passive"))
      (node (ref "T2") (pin "1") (pinfunction "E_1") (pintype "passive"))
      (node (ref "U$3") (pin "P2") (pinfunction "P2_P2") (pintype "bidirectional"))
      (node (ref "U$7") (pin "P2") (pinfunction "P2_P2") (pintype "bidirectional"))
    )
    (net (code "24") (name "HALL1") (class "Default")
      (node (ref "HALL1") (pin "3") (pinfunction "3_3") (pintype "passive"))
      (node (ref "R12") (pin "2") (pinfunction "2_2") (pintype "passive"))
      (node (ref "U7") (pin "32") (pinfunction "PD2(INT0)_32") (pintype "bidirectional"))
    )
    (net (code "25") (name "HALL1_B") (class "Default")
      (node (ref "HALL1_B") (pin "3") (pinfunction "3_3") (pintype "passive"))
      (node (ref "R14") (pin "2") (pinfunction "2_2") (pintype "passive"))
      (node (ref "U$1") (pin "1/TX") (pinfunction "1/TX_1/TX") (pintype "bidirectional"))
    )
    (net (code "26") (name "HALL2") (class "Default")
      (node (ref "HALL2") (pin "3") (pinfunction "3_3") (pintype "passive"))
      (node (ref "R13") (pin "2") (pinfunction "2_2") (pintype "passive"))
      (node (ref "U7") (pin "1") (pinfunction "PD3(INT1)_1") (pintype "bidirectional"))
    )
    (net (code "27") (name "HALL2_B") (class "Default")
      (node (ref "HALL2_B") (pin "3") (pinfunction "3_3") (pintype "passive"))
      (node (ref "R15") (pin "2") (pinfunction "2_2") (pintype "passive"))
      (node (ref "U$1") (pin "2") (pinfunction "2_2") (pintype "bidirectional"))
    )
    (net (code "28") (name "HI1") (class "Default")
      (node (ref "SV2") (pin "1") (pinfunction "1_1") (pintype "passive"))
      (node (ref "U$1") (pin "3/CANTX") (pinfunction "3/CANTX_3/CANTX") (pintype "bidirectional"))
    )
    (net (code "29") (name "HI1_TOP") (class "Default")
      (node (ref "GATE1") (pin "5") (pinfunction "HI_5") (pintype "input"))
      (node (ref "SV6") (pin "1") (pinfunction "1_1") (pintype "passive"))
    )
    (net (code "30") (name "HI2") (class "Default")
      (node (ref "SV2") (pin "3") (pinfunction "3_3") (pintype "passive"))
      (node (ref "U$1") (pin "5") (pinfunction "5_5") (pintype "bidirectional"))
    )
    (net (code "31") (name "HI2_TOP") (class "Default")
      (node (ref "GATE2") (pin "6") (pinfunction "LI_6") (pintype "input"))
      (node (ref "SV6") (pin "3") (pinfunction "3_3") (pintype "passive"))
    )
    (net (code "32") (name "LED1") (class "Default")
      (node (ref "R9") (pin "2") (pinfunction "2_2") (pintype "passive"))
      (node (ref "U$1") (pin "14/A0") (pinfunction "14/A0_14/A0") (pintype "bidirectional"))
    )
    (net (code "33") (name "LED1HI") (class "Default")
      (node (ref "LED1") (pin "POSITIVE") (pinfunction "POSITIVE_POSITIVE") (pintype "bidirectional"))
      (node (ref "LED1") (pin "POSITIVE1") (pinfunction "POSITIVE_POSITIVE1") (pintype "bidirectional"))
      (node (ref "LED1_CONN2") (pin "2") (pinfunction "2_2") (pintype "passive"))
    )
    (net (code "34") (name "LED1LO") (class "Default")
      (node (ref "LED1") (pin "NEGATIVE") (pinfunction "NEGATIVE_NEGATIVE") (pintype "bidirectional"))
      (node (ref "LED1") (pin "NEGATIVE1") (pinfunction "NEGATIVE_NEGATIVE1") (pintype "bidirectional"))
      (node (ref "LED1_CONN2") (pin "1") (pinfunction "1_1") (pintype "passive"))
    )
    (net (code "35") (name "LED2") (class "Default")
      (node (ref "R10") (pin "2") (pinfunction "2_2") (pintype "passive"))
      (node (ref "U$1") (pin "15/A1") (pinfunction "15/A1_15/A1") (pintype "bidirectional"))
    )
    (net (code "36") (name "LED2HI") (class "Default")
      (node (ref "LED2") (pin "POSITIVE") (pinfunction "POSITIVE_POSITIVE") (pintype "bidirectional"))
      (node (ref "LED2") (pin "POSITIVE1") (pinfunction "POSITIVE_POSITIVE1") (pintype "bidirectional"))
      (node (ref "LED2_CONN2") (pin "2") (pinfunction "2_2") (pintype "passive"))
    )
    (net (code "37") (name "LED2LO") (class "Default")
      (node (ref "LED2") (pin "NEGATIVE") (pinfunction "NEGATIVE_NEGATIVE") (pintype "bidirectional"))
      (node (ref "LED2") (pin "NEGATIVE1") (pinfunction "NEGATIVE_NEGATIVE1") (pintype "bidirectional"))
      (node (ref "LED2_CONN2") (pin "1") (pinfunction "1_1") (pintype "passive"))
    )
    (net (code "38") (name "LED3") (class "Default")
      (node (ref "R11") (pin "2") (pinfunction "2_2") (pintype "passive"))
      (node (ref "U$1") (pin "16/A2") (pinfunction "16/A2_16/A2") (pintype "bidirectional"))
    )
    (net (code "39") (name "LI1") (class "Default")
      (node (ref "SV2") (pin "2") (pinfunction "2_2") (pintype "passive"))
      (node (ref "U$1") (pin "4/CANRX") (pinfunction "4/CANRX_4/CANRX") (pintype "bidirectional"))
    )
    (net (code "40") (name "LI1_TOP") (class "Default")
      (node (ref "GATE1") (pin "6") (pinfunction "LI_6") (pintype "input"))
      (node (ref "SV6") (pin "2") (pinfunction "2_2") (pintype "passive"))
    )
    (net (code "41") (name "LI2") (class "Default")
      (node (ref "SV2") (pin "4") (pinfunction "4_4") (pintype "passive"))
      (node (ref "U$1") (pin "6") (pinfunction "6_6") (pintype "bidirectional"))
    )
    (net (code "42") (name "LI2_TOP") (class "Default")
      (node (ref "GATE2") (pin "5") (pinfunction "HI_5") (pintype "input"))
      (node (ref "SV6") (pin "4") (pinfunction "4_4") (pintype "passive"))
    )
    (net (code "43") (name "MOTOR_HIGH") (class "Default")
      (node (ref "R3") (pin "2") (pinfunction "2_2") (pintype "passive"))
      (node (ref "SV2") (pin "5") (pinfunction "5_5") (pintype "passive"))
    )
    (net (code "44") (name "MOTOR_HIGH_TOP") (class "Default")
      (node (ref "BOT_REV") (pin "2") (pinfunction "DRAIN_2") (pintype "passive"))
      (node (ref "MOTOR_POS") (pin "MP") (pinfunction "MP_MP") (pintype "passive"))
      (node (ref "SV6") (pin "5") (pinfunction "5_5") (pintype "passive"))
      (node (ref "TOP_FWD") (pin "3") (pinfunction "SOURCE_3") (pintype "passive"))
    )
    (net (code "45") (name "MOTOR_LOW") (class "Default")
      (node (ref "R4") (pin "1") (pinfunction "1_1") (pintype "passive"))
      (node (ref "S1") (pin "8") (pinfunction "8_8") (pintype "passive"))
      (node (ref "SV2") (pin "6") (pinfunction "6_6") (pintype "passive"))
    )
    (net (code "46") (name "MOTOR_LOW_TOP") (class "Default")
      (node (ref "BOT_FWD") (pin "2") (pinfunction "DRAIN_2") (pintype "passive"))
      (node (ref "MOTOR_NEG") (pin "MP") (pinfunction "MP_MP") (pintype "passive"))
      (node (ref "SV6") (pin "6") (pinfunction "6_6") (pintype "passive"))
      (node (ref "TOP_REV") (pin "3") (pinfunction "SOURCE_3") (pintype "passive"))
    )
    (net (code "47") (name "Net-(BIG_SWITCH-PadVCC)") (class "Default")
      (node (ref "BIG_SWITCH") (pin "VCC") (pinfunction "VCC_VCC") (pintype "power_in"))
      (node (ref "C12") (pin "+") (pinfunction "+_+") (pintype "passive"))
      (node (ref "C13") (pin "+") (pinfunction "+_+") (pintype "passive"))
      (node (ref "C14") (pin "+") (pinfunction "+_+") (pintype "passive"))
      (node (ref "C15") (pin "+") (pinfunction "+_+") (pintype "passive"))
      (node (ref "FUSE") (pin "B") (pinfunction "GND_B") (pintype "power_in"))
      (node (ref "FUSE") (pin "D") (pinfunction "GND_D") (pintype "power_in"))
      (node (ref "R16") (pin "2") (pinfunction "2_2") (pintype "passive"))
    )
    (net (code "48") (name "Net-(BOT_FWD-GATE)") (class "Default")
      (node (ref "BOT_FWD") (pin "1") (pinfunction "GATE_1") (pintype "passive"))
      (node (ref "GATE2") (pin "8") (pinfunction "LO_8") (pintype "output"))
    )
    (net (code "49") (name "Net-(BOT_REV-GATE)") (class "Default")
      (node (ref "BOT_REV") (pin "1") (pinfunction "GATE_1") (pintype "passive"))
      (node (ref "GATE1") (pin "8") (pinfunction "LO_8") (pintype "output"))
    )
    (net (code "50") (name "Net-(D1-PadA)") (class "Default")
      (node (ref "D1") (pin "A") (pinfunction "A_A") (pintype "passive"))
      (node (ref "R9") (pin "1") (pinfunction "1_1") (pintype "passive"))
    )
    (net (code "51") (name "Net-(D2-PadA)") (class "Default")
      (node (ref "D2") (pin "A") (pinfunction "A_A") (pintype "passive"))
      (node (ref "R10") (pin "1") (pinfunction "1_1") (pintype "passive"))
    )
    (net (code "52") (name "Net-(D5-PadA)") (class "Default")
      (node (ref "D5") (pin "A") (pinfunction "A_A") (pintype "passive"))
      (node (ref "R11") (pin "1") (pinfunction "1_1") (pintype "passive"))
    )
    (net (code "53") (name "Net-(GATE1-HB)") (class "Default")
      (node (ref "C1") (pin "2") (pinfunction "2_2") (pintype "passive"))
      (node (ref "C2") (pin "2") (pinfunction "2_2") (pintype "passive"))
      (node (ref "D3") (pin "C") (pinfunction "C_C") (pintype "passive"))
      (node (ref "GATE1") (pin "2") (pinfunction "HB_2") (pintype "passive"))
    )
    (net (code "54") (name "Net-(GATE1-HO)") (class "Default")
      (node (ref "GATE1") (pin "3") (pinfunction "HO_3") (pintype "output"))
      (node (ref "TOP_FWD") (pin "1") (pinfunction "GATE_1") (pintype "passive"))
    )
    (net (code "55") (name "Net-(GATE1-HS)") (class "Default")
      (node (ref "C1") (pin "1") (pinfunction "1_1") (pintype "passive"))
      (node (ref "C2") (pin "1") (pinfunction "1_1") (pintype "passive"))
      (node (ref "GATE1") (pin "4") (pinfunction "HS_4") (pintype "passive"))
    )
    (net (code "56") (name "Net-(GATE2-HB)") (class "Default")
      (node (ref "C3") (pin "2") (pinfunction "2_2") (pintype "passive"))
      (node (ref "C4") (pin "2") (pinfunction "2_2") (pintype "passive"))
      (node (ref "D4") (pin "C") (pinfunction "C_C") (pintype "passive"))
      (node (ref "GATE2") (pin "2") (pinfunction "HB_2") (pintype "passive"))
    )
    (net (code "57") (name "Net-(GATE2-HO)") (class "Default")
      (node (ref "GATE2") (pin "3") (pinfunction "HO_3") (pintype "output"))
      (node (ref "TOP_REV") (pin "1") (pinfunction "GATE_1") (pintype "passive"))
    )
    (net (code "58") (name "Net-(GATE2-HS)") (class "Default")
      (node (ref "C3") (pin "1") (pinfunction "1_1") (pintype "passive"))
      (node (ref "C4") (pin "1") (pinfunction "1_1") (pintype "passive"))
      (node (ref "GATE2") (pin "4") (pinfunction "HS_4") (pintype "passive"))
    )
    (net (code "59") (name "Net-(LED_DRIVER1-DRAIN)") (class "Default")
      (node (ref "LED2_CONN") (pin "1") (pinfunction "1_1") (pintype "passive"))
      (node (ref "LED_DRIVER1") (pin "2") (pinfunction "DRAIN_2") (pintype "passive"))
    )
    (net (code "60") (name "Net-(LED_DRIVER1-GATE)") (class "Default")
      (node (ref "LED_DRIVER1") (pin "1") (pinfunction "GATE_1") (pintype "passive"))
      (node (ref "R8") (pin "P$1") (pinfunction "1_P$1") (pintype "passive"))
      (node (ref "T2") (pin "3") (pinfunction "C_3") (pintype "passive"))
    )
    (net (code "61") (name "Net-(LED_DRIVER1-SOURCE)") (class "Default")
      (node (ref "LED_DRIVER1") (pin "3") (pinfunction "SOURCE_3") (pintype "passive"))
      (node (ref "R7") (pin "2") (pinfunction "2_2") (pintype "passive"))
      (node (ref "T2") (pin "2") (pinfunction "B_2") (pintype "passive"))
    )
    (net (code "62") (name "Net-(LED_DRIVER2-DRAIN)") (class "Default")
      (node (ref "LED1_CONN") (pin "1") (pinfunction "1_1") (pintype "passive"))
      (node (ref "LED_DRIVER2") (pin "2") (pinfunction "DRAIN_2") (pintype "passive"))
    )
    (net (code "63") (name "Net-(LED_DRIVER2-GATE)") (class "Default")
      (node (ref "LED_DRIVER2") (pin "1") (pinfunction "GATE_1") (pintype "passive"))
      (node (ref "R6") (pin "P$1") (pinfunction "1_P$1") (pintype "passive"))
      (node (ref "T1") (pin "3") (pinfunction "C_3") (pintype "passive"))
    )
    (net (code "64") (name "Net-(LED_DRIVER2-SOURCE)") (class "Default")
      (node (ref "LED_DRIVER2") (pin "3") (pinfunction "SOURCE_3") (pintype "passive"))
      (node (ref "R5") (pin "2") (pinfunction "2_2") (pintype "passive"))
      (node (ref "T1") (pin "2") (pinfunction "B_2") (pintype "passive"))
    )
    (net (code "65") (name "Net-(R5-Pad1)") (class "Default")
      (node (ref "R5") (pin "1") (pinfunction "1_1") (pintype "passive"))
      (node (ref "U$7") (pin "P3") (pinfunction "P3_P3") (pintype "bidirectional"))
    )
    (net (code "66") (name "Net-(R7-Pad1)") (class "Default")
      (node (ref "R7") (pin "1") (pinfunction "1_1") (pintype "passive"))
      (node (ref "U$3") (pin "P3") (pinfunction "P3_P3") (pintype "bidirectional"))
    )
    (net (code "67") (name "Net-(U7-PB6(XTAL1{slash}TOSC1))") (class "Default")
      (node (ref "C6") (pin "1") (pinfunction "1_1") (pintype "passive"))
      (node (ref "U7") (pin "7") (pinfunction "PB6(XTAL1/TOSC1)_7") (pintype "bidirectional"))
      (node (ref "Y1") (pin "1") (pinfunction "1_1") (pintype "passive"))
    )
    (net (code "68") (name "Net-(U7-PB7(XTAL2{slash}TOSC2))") (class "Default")
      (node (ref "C5") (pin "1") (pinfunction "1_1") (pintype "passive"))
      (node (ref "U7") (pin "8") (pinfunction "PB7(XTAL2/TOSC2)_8") (pintype "bidirectional"))
      (node (ref "Y1") (pin "2") (pinfunction "2_2") (pintype "passive"))
    )
    (net (code "69") (name "PB1") (class "Default")
      (node (ref "ATGPIO") (pin "10") (pinfunction "10_10") (pintype "passive"))
      (node (ref "U7") (pin "13") (pinfunction "PB1(OC1A)_13") (pintype "bidirectional"))
    )
    (net (code "70") (name "PC1") (class "Default")
      (node (ref "ATGPIO") (pin "1") (pinfunction "1_1") (pintype "passive"))
      (node (ref "U7") (pin "24") (pinfunction "PC1(ADC1)_24") (pintype "bidirectional"))
    )
    (net (code "71") (name "PC2") (class "Default")
      (node (ref "ATGPIO") (pin "2") (pinfunction "2_2") (pintype "passive"))
      (node (ref "U7") (pin "25") (pinfunction "PC2(ADC2)_25") (pintype "bidirectional"))
    )
    (net (code "72") (name "PC3") (class "Default")
      (node (ref "ATGPIO") (pin "3") (pinfunction "3_3") (pintype "passive"))
      (node (ref "U7") (pin "26") (pinfunction "PC3(ADC3)_26") (pintype "bidirectional"))
    )
    (net (code "73") (name "PC4") (class "Default")
      (node (ref "ATGPIO") (pin "4") (pinfunction "4_4") (pintype "passive"))
      (node (ref "U7") (pin "27") (pinfunction "PC4(ADC4/SDA)_27") (pintype "bidirectional"))
    )
    (net (code "74") (name "PC5") (class "Default")
      (node (ref "ATGPIO") (pin "5") (pinfunction "5_5") (pintype "passive"))
      (node (ref "U7") (pin "28") (pinfunction "PC5(ADC5/SCL)_28") (pintype "bidirectional"))
    )
    (net (code "75") (name "PD4") (class "Default")
      (node (ref "ATGPIO") (pin "8") (pinfunction "8_8") (pintype "passive"))
      (node (ref "U7") (pin "2") (pinfunction "PD4(XCK/T0)_2") (pintype "bidirectional"))
    )
    (net (code "76") (name "PD5") (class "Default")
      (node (ref "ATGPIO") (pin "9") (pinfunction "9_9") (pintype "passive"))
      (node (ref "U7") (pin "9") (pinfunction "PD5(T1)_9") (pintype "bidirectional"))
    )
    (net (code "77") (name "PD6") (class "Default")
      (node (ref "U7") (pin "10") (pinfunction "PD6(AIN0)_10") (pintype "bidirectional"))
    )
    (net (code "78") (name "REC_EXTRA1") (class "Default")
      (node (ref "REC") (pin "5") (pinfunction "5_5") (pintype "passive"))
      (node (ref "U$1") (pin "22/A8") (pinfunction "22/A8_22/A8") (pintype "bidirectional"))
    )
    (net (code "79") (name "REC_EXTRA2") (class "Default")
      (node (ref "REC") (pin "6") (pinfunction "6_6") (pintype "passive"))
      (node (ref "U$1") (pin "23/A9") (pinfunction "23/A9_23/A9") (pintype "bidirectional"))
    )
    (net (code "80") (name "REC_MOTOR") (class "Default")
      (node (ref "REC") (pin "4") (pinfunction "4_4") (pintype "passive"))
      (node (ref "U$1") (pin "21/A7") (pinfunction "21/A7_21/A7") (pintype "bidirectional"))
    )
    (net (code "81") (name "REC_SERVO") (class "Default")
      (node (ref "REC") (pin "3") (pinfunction "3_3") (pintype "passive"))
      (node (ref "U$1") (pin "20/A6") (pinfunction "20/A6_20/A6") (pintype "bidirectional"))
    )
    (net (code "82") (name "RX") (class "Default")
      (node (ref "TXRX") (pin "1") (pinfunction "1_1") (pintype "passive"))
      (node (ref "U7") (pin "30") (pinfunction "PD0(RXD)_30") (pintype "bidirectional"))
    )
    (net (code "83") (name "SERVO") (class "Default")
      (node (ref "SERVO") (pin "3") (pinfunction "3_3") (pintype "passive"))
      (node (ref "U$1") (pin "9/CS") (pinfunction "9/CS_9/CS") (pintype "bidirectional"))
    )
    (net (code "84") (name "SPI_MISO") (class "Default")
      (node (ref "U$1") (pin "11/MOSI") (pinfunction "11/MOSI_11/MOSI") (pintype "bidirectional"))
      (node (ref "U7") (pin "16") (pinfunction "PB4(MISO)_16") (pintype "bidirectional"))
    )
    (net (code "85") (name "SPI_MOSI") (class "Default")
      (node (ref "U$1") (pin "12/MISO") (pinfunction "12/MISO_12/MISO") (pintype "bidirectional"))
      (node (ref "U7") (pin "15") (pinfunction "PB3(MOSI/OC2)_15") (pintype "bidirectional"))
    )
    (net (code "86") (name "SPI_SCK") (class "Default")
      (node (ref "U$1") (pin "13/SCK") (pinfunction "13/SCK_13/SCK") (pintype "bidirectional"))
      (node (ref "U7") (pin "17") (pinfunction "PB5(SCK)_17") (pintype "bidirectional"))
    )
    (net (code "87") (name "SPI_SS") (class "Default")
      (node (ref "U$1") (pin "10/CS") (pinfunction "10/CS_10/CS") (pintype "bidirectional"))
      (node (ref "U7") (pin "14") (pinfunction "PB2(SS/OC1B)_14") (pintype "bidirectional"))
    )
    (net (code "88") (name "SW1") (class "Default")
      (node (ref "S1") (pin "1") (pinfunction "1_1") (pintype "passive"))
      (node (ref "U$1") (pin "24") (pinfunction "24_24") (pintype "bidirectional"))
    )
    (net (code "89") (name "SW2") (class "Default")
      (node (ref "S1") (pin "2") (pinfunction "2_2") (pintype "passive"))
      (node (ref "U$1") (pin "25") (pinfunction "25_25") (pintype "bidirectional"))
    )
    (net (code "90") (name "SW3") (class "Default")
      (node (ref "S1") (pin "3") (pinfunction "3_3") (pintype "passive"))
      (node (ref "U$1") (pin "26") (pinfunction "26_26") (pintype "bidirectional"))
    )
    (net (code "91") (name "SW4") (class "Default")
      (node (ref "S1") (pin "4") (pinfunction "4_4") (pintype "passive"))
      (node (ref "U$1") (pin "27") (pinfunction "27_27") (pintype "bidirectional"))
    )
    (net (code "92") (name "SW5") (class "Default")
      (node (ref "U$1") (pin "28") (pinfunction "28_28") (pintype "bidirectional"))
    )
    (net (code "93") (name "TGPIO1") (class "Default")
      (node (ref "TGPIO") (pin "1") (pinfunction "1_1") (pintype "passive"))
      (node (ref "U$1") (pin "33/A14") (pinfunction "33/A14_33/A14") (pintype "bidirectional"))
    )
    (net (code "94") (name "TGPIO2") (class "Default")
      (node (ref "TGPIO") (pin "2") (pinfunction "2_2") (pintype "passive"))
      (node (ref "U$1") (pin "34/A15") (pinfunction "34/A15_34/A15") (pintype "bidirectional"))
    )
    (net (code "95") (name "TGPIO3") (class "Default")
      (node (ref "TGPIO") (pin "3") (pinfunction "3_3") (pintype "passive"))
      (node (ref "U$1") (pin "35/A16") (pinfunction "35/A16_35/A16") (pintype "bidirectional"))
    )
    (net (code "96") (name "TGPIO4") (class "Default")
      (node (ref "TGPIO") (pin "4") (pinfunction "4_4") (pintype "passive"))
      (node (ref "U$1") (pin "36/A17") (pinfunction "36/A17_36/A17") (pintype "bidirectional"))
    )
    (net (code "97") (name "TGPIO5") (class "Default")
      (node (ref "TGPIO") (pin "5") (pinfunction "5_5") (pintype "passive"))
      (node (ref "U$1") (pin "37/A18") (pinfunction "37/A18_37/A18") (pintype "bidirectional"))
    )
    (net (code "98") (name "TGPIO6") (class "Default")
      (node (ref "TGPIO") (pin "6") (pinfunction "6_6") (pintype "passive"))
      (node (ref "U$1") (pin "38/A19") (pinfunction "38/A19_38/A19") (pintype "bidirectional"))
    )
    (net (code "99") (name "TGPIO7") (class "Default")
      (node (ref "TGPIO") (pin "7") (pinfunction "7_7") (pintype "passive"))
      (node (ref "U$1") (pin "39/A20") (pinfunction "39/A20_39/A20") (pintype "bidirectional"))
    )
    (net (code "100") (name "TGPIO8") (class "Default")
      (node (ref "TGPIO") (pin "8") (pinfunction "8_8") (pintype "passive"))
      (node (ref "U$1") (pin "21/DAC0") (pinfunction "A21/DAC0_21/DAC0") (pintype "bidirectional"))
    )
    (net (code "101") (name "TGPIO9") (class "Default")
      (node (ref "TGPIO") (pin "9") (pinfunction "9_9") (pintype "passive"))
      (node (ref "U$1") (pin "A22/DAC1") (pinfunction "A22/DAC1_A22/DAC1") (pintype "bidirectional"))
    )
    (net (code "102") (name "TX") (class "Default")
      (node (ref "TXRX") (pin "2") (pinfunction "2_2") (pintype "passive"))
      (node (ref "U7") (pin "31") (pinfunction "PD1(TXD)_31") (pintype "bidirectional"))
    )
    (net (code "103") (name "unconnected-(LED1-PadTHERMAL)") (class "Default")
      (node (ref "LED1") (pin "THERMAL") (pinfunction "THERMAL_THERMAL") (pintype "bidirectional"))
    )
    (net (code "104") (name "unconnected-(LED2-PadTHERMAL)") (class "Default")
      (node (ref "LED2") (pin "THERMAL") (pinfunction "THERMAL_THERMAL") (pintype "bidirectional"))
    )
    (net (code "105") (name "unconnected-(SV1-Pad1)") (class "Default")
      (node (ref "SV1") (pin "1") (pinfunction "1_1") (pintype "passive"))
    )
    (net (code "106") (name "unconnected-(SV1-Pad2)") (class "Default")
      (node (ref "SV1") (pin "2") (pinfunction "2_2") (pintype "passive"))
    )
    (net (code "107") (name "unconnected-(SV1-Pad3)") (class "Default")
      (node (ref "SV1") (pin "3") (pinfunction "3_3") (pintype "passive"))
    )
    (net (code "108") (name "unconnected-(SV1-Pad4)") (class "Default")
      (node (ref "SV1") (pin "4") (pinfunction "4_4") (pintype "passive"))
    )
    (net (code "109") (name "unconnected-(SV1-Pad5)") (class "Default")
      (node (ref "SV1") (pin "5") (pinfunction "5_5") (pintype "passive"))
    )
    (net (code "110") (name "unconnected-(SV1-Pad6)") (class "Default")
      (node (ref "SV1") (pin "6") (pinfunction "6_6") (pintype "passive"))
    )
    (net (code "111") (name "unconnected-(SV1-Pad8)") (class "Default")
      (node (ref "SV1") (pin "8") (pinfunction "8_8") (pintype "passive"))
    )
    (net (code "112") (name "unconnected-(SV1-Pad9)") (class "Default")
      (node (ref "SV1") (pin "9") (pinfunction "9_9") (pintype "passive"))
    )
    (net (code "113") (name "unconnected-(SV2-Pad7)") (class "Default")
      (node (ref "SV2") (pin "7") (pinfunction "7_7") (pintype "passive"))
    )
    (net (code "114") (name "unconnected-(SV2-Pad8)") (class "Default")
      (node (ref "SV2") (pin "8") (pinfunction "8_8") (pintype "passive"))
    )
    (net (code "115") (name "unconnected-(SV2-Pad9)") (class "Default")
      (node (ref "SV2") (pin "9") (pinfunction "9_9") (pintype "passive"))
    )
    (net (code "116") (name "unconnected-(SV2-Pad10)") (class "Default")
      (node (ref "SV2") (pin "10") (pinfunction "10_10") (pintype "passive"))
    )
    (net (code "117") (name "unconnected-(SV3-Pad1)") (class "Default")
      (node (ref "SV3") (pin "1") (pinfunction "1_1") (pintype "passive"))
    )
    (net (code "118") (name "unconnected-(SV3-Pad2)") (class "Default")
      (node (ref "SV3") (pin "2") (pinfunction "2_2") (pintype "passive"))
    )
    (net (code "119") (name "unconnected-(SV3-Pad3)") (class "Default")
      (node (ref "SV3") (pin "3") (pinfunction "3_3") (pintype "passive"))
    )
    (net (code "120") (name "unconnected-(SV3-Pad4)") (class "Default")
      (node (ref "SV3") (pin "4") (pinfunction "4_4") (pintype "passive"))
    )
    (net (code "121") (name "unconnected-(SV4-Pad1)") (class "Default")
      (node (ref "SV4") (pin "1") (pinfunction "1_1") (pintype "passive"))
    )
    (net (code "122") (name "unconnected-(SV4-Pad2)") (class "Default")
      (node (ref "SV4") (pin "2") (pinfunction "2_2") (pintype "passive"))
    )
    (net (code "123") (name "unconnected-(SV4-Pad3)") (class "Default")
      (node (ref "SV4") (pin "3") (pinfunction "3_3") (pintype "passive"))
    )
    (net (code "124") (name "unconnected-(SV4-Pad4)") (class "Default")
      (node (ref "SV4") (pin "4") (pinfunction "4_4") (pintype "passive"))
    )
    (net (code "125") (name "unconnected-(SV6-Pad7)") (class "Default")
      (node (ref "SV6") (pin "7") (pinfunction "7_7") (pintype "passive"))
    )
    (net (code "126") (name "unconnected-(SV6-Pad8)") (class "Default")
      (node (ref "SV6") (pin "8") (pinfunction "8_8") (pintype "passive"))
    )
    (net (code "127") (name "unconnected-(SV6-Pad9)") (class "Default")
      (node (ref "SV6") (pin "9") (pinfunction "9_9") (pintype "passive"))
    )
    (net (code "128") (name "unconnected-(SV6-Pad10)") (class "Default")
      (node (ref "SV6") (pin "10") (pinfunction "10_10") (pintype "passive"))
    )
    (net (code "129") (name "unconnected-(SV7-Pad1)") (class "Default")
      (node (ref "SV7") (pin "1") (pinfunction "1_1") (pintype "passive"))
    )
    (net (code "130") (name "unconnected-(SV7-Pad2)") (class "Default")
      (node (ref "SV7") (pin "2") (pinfunction "2_2") (pintype "passive"))
    )
    (net (code "131") (name "unconnected-(SV7-Pad3)") (class "Default")
      (node (ref "SV7") (pin "3") (pinfunction "3_3") (pintype "passive"))
    )
    (net (code "132") (name "unconnected-(SV7-Pad4)") (class "Default")
      (node (ref "SV7") (pin "4") (pinfunction "4_4") (pintype "passive"))
    )
    (net (code "133") (name "unconnected-(SV8-Pad1)") (class "Default")
      (node (ref "SV8") (pin "1") (pinfunction "1_1") (pintype "passive"))
    )
    (net (code "134") (name "unconnected-(SV8-Pad2)") (class "Default")
      (node (ref "SV8") (pin "2") (pinfunction "2_2") (pintype "passive"))
    )
    (net (code "135") (name "unconnected-(SV8-Pad3)") (class "Default")
      (node (ref "SV8") (pin "3") (pinfunction "3_3") (pintype "passive"))
    )
    (net (code "136") (name "unconnected-(SV8-Pad4)") (class "Default")
      (node (ref "SV8") (pin "4") (pinfunction "4_4") (pintype "passive"))
    )
    (net (code "137") (name "unconnected-(U$1-Pad0{slash}RX)") (class "Default")
      (node (ref "U$1") (pin "0/RX") (pinfunction "0/RX_0/RX") (pintype "bidirectional"))
    )
    (net (code "138") (name "unconnected-(U$1-Pad3V3)") (class "Default")
      (node (ref "U$1") (pin "3V3") (pinfunction "3V3_3V3") (pintype "bidirectional"))
    )
    (net (code "139") (name "unconnected-(U$1-Pad32{slash}A13)") (class "Default")
      (node (ref "U$1") (pin "32/A13") (pinfunction "32/A13_32/A13") (pintype "bidirectional"))
    )
    (net (code "140") (name "unconnected-(U$1-PadA10)") (class "Default")
      (node (ref "U$1") (pin "A10") (pinfunction "A10_A10") (pintype "bidirectional"))
    )
    (net (code "141") (name "unconnected-(U$1-PadA11)") (class "Default")
      (node (ref "U$1") (pin "A11") (pinfunction "A11_A11") (pintype "bidirectional"))
    )
    (net (code "142") (name "unconnected-(U$1-PadAREF)") (class "Default")
      (node (ref "U$1") (pin "AREF") (pinfunction "AREF_AREF") (pintype "bidirectional"))
    )
    (net (code "143") (name "unconnected-(U$1-PadVUSB)") (class "Default")
      (node (ref "U$1") (pin "VUSB") (pinfunction "VUSB_VUSB") (pintype "bidirectional"))
    )
    (net (code "144") (name "unconnected-(U$3-PadP1)") (class "Default")
      (node (ref "U$3") (pin "P1") (pinfunction "P1_P1") (pintype "bidirectional"))
    )
    (net (code "145") (name "unconnected-(U$7-PadP1)") (class "Default")
      (node (ref "U$7") (pin "P1") (pinfunction "P1_P1") (pintype "bidirectional"))
    )
    (net (code "146") (name "unconnected-(U7-AREF-Pad20)") (class "Default")
      (node (ref "U7") (pin "20") (pinfunction "AREF_20") (pintype "bidirectional"))
    )
  )
)
